# openbook_schematic.net
KiCad netlist of a schematic drawn in EAGLE
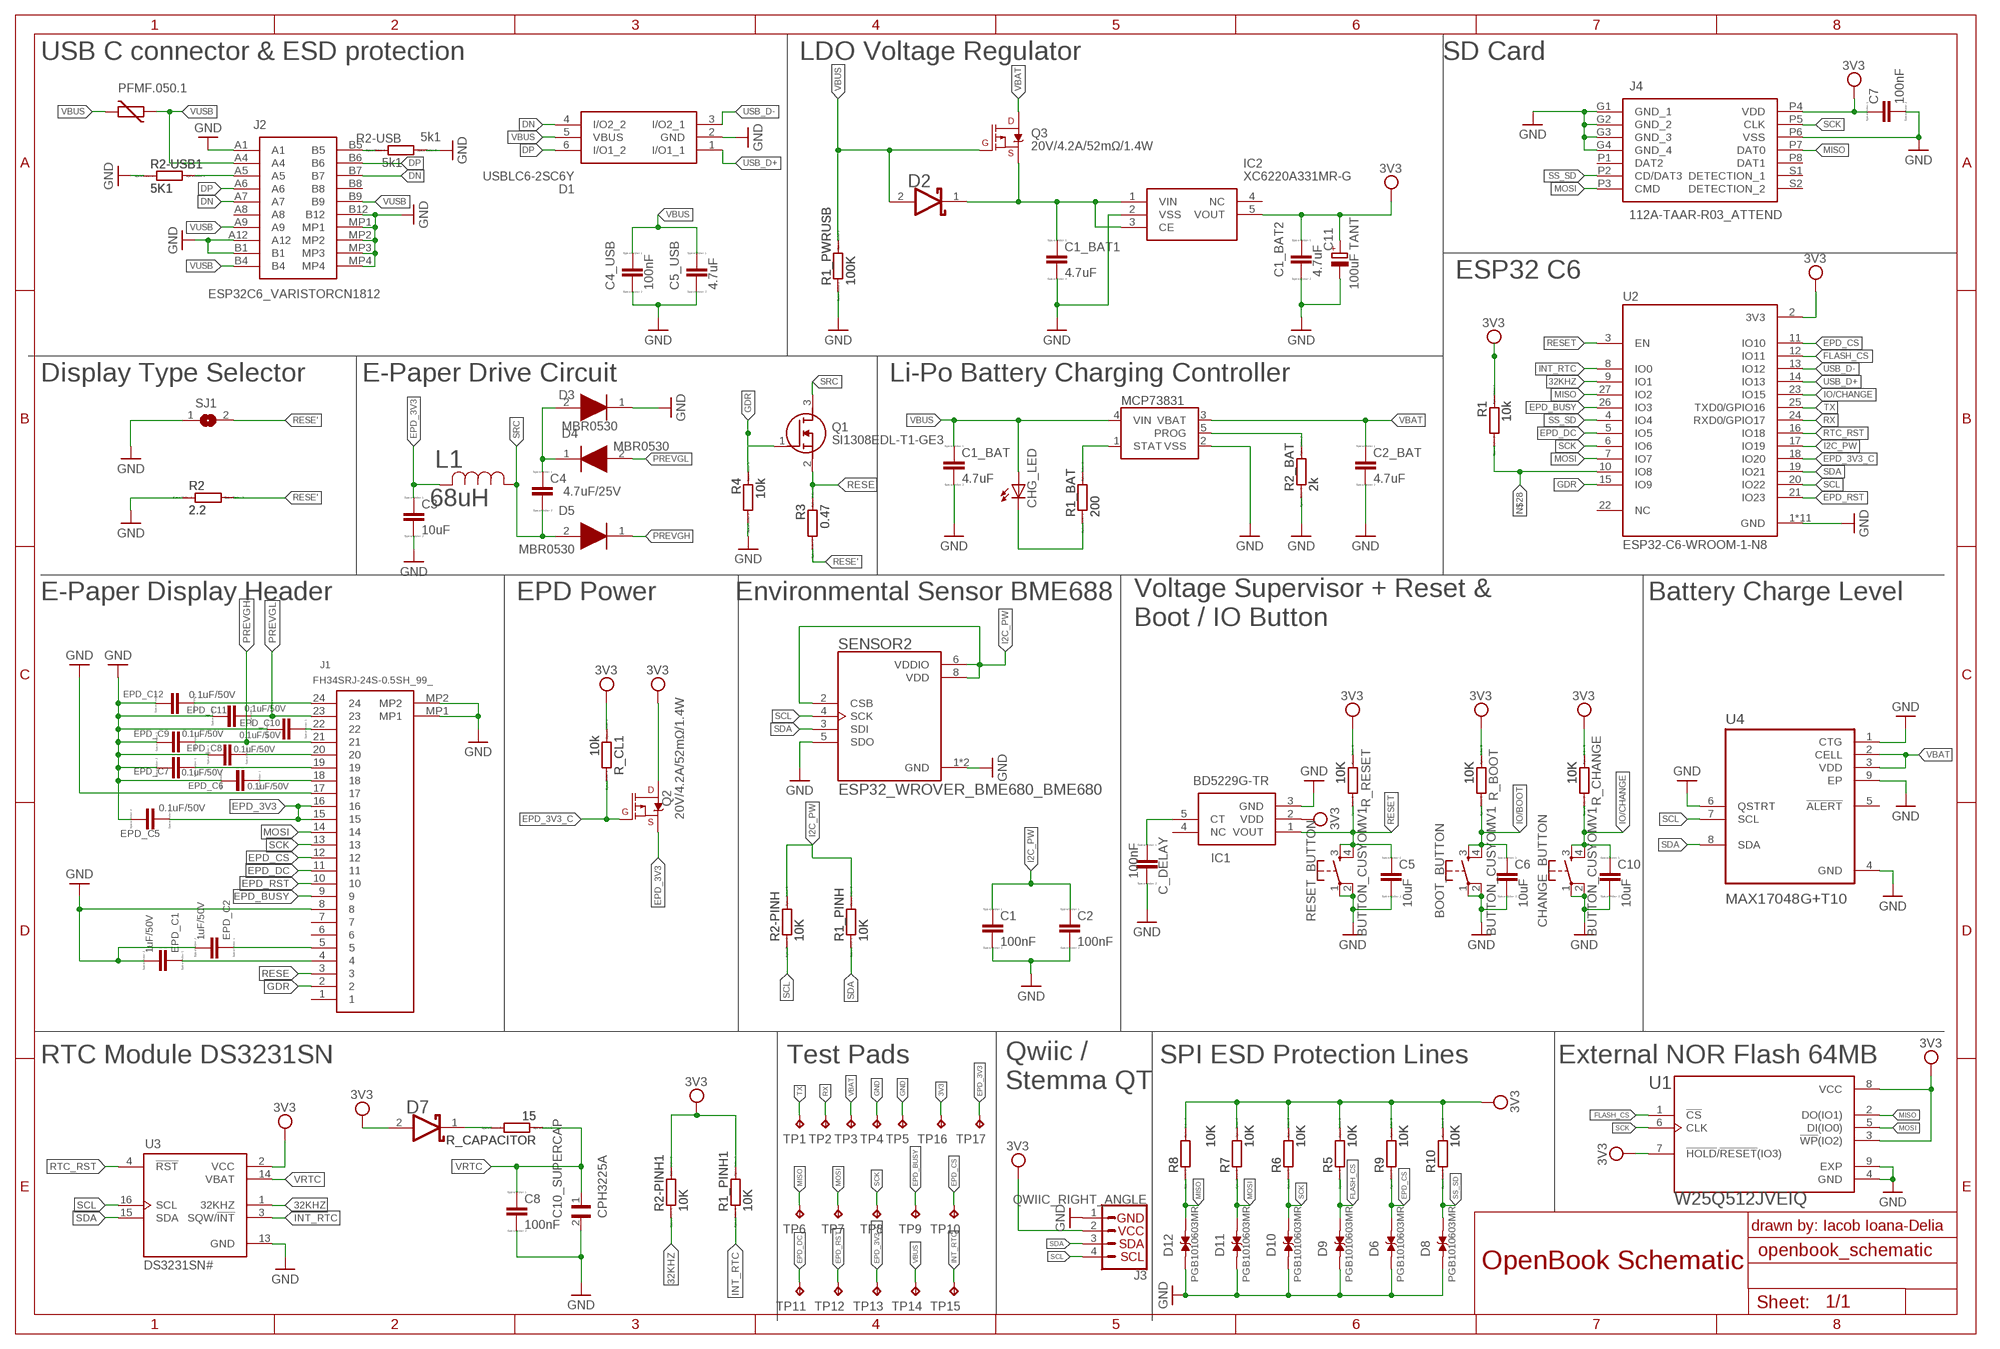
[diagram p0: schematic, sheet 1]

(export (version "E")
  (design (tool "Eeschema 10.0.6"))
  (components
    (comp (ref "BOOT_BUTTON")
      (value "BUTTON_CUSYOMV1")
      (footprint "eagle-import:MYBUTTON")
      (libsource (lib "eagle-import") (part "BUTTON_CUSYOMV1"))
    )
    (comp (ref "C1")
      (value "100nF")
      (footprint "eagle-import:ESP32_WROVER_EAGLE-LTSPICE_C0402")
      (libsource (lib "eagle-import") (part "ESP32_WROVER_EAGLE-LTSPICE_CC0402"))
    )
    (comp (ref "C1_BAT")
      (value "4.7uF")
      (footprint "eagle-import:ESP32_WROVER_EAGLE-LTSPICE_C0402")
      (libsource (lib "eagle-import") (part "ESP32_WROVER_EAGLE-LTSPICE_CC0402"))
    )
    (comp (ref "C1_BAT1")
      (value "4.7uF")
      (footprint "eagle-import:ESP32_WROVER_EAGLE-LTSPICE_C0402")
      (libsource (lib "eagle-import") (part "ESP32_WROVER_EAGLE-LTSPICE_CC0402"))
    )
    (comp (ref "C1_BAT2")
      (value "4.7uF")
      (footprint "eagle-import:ESP32_WROVER_EAGLE-LTSPICE_C0402")
      (libsource (lib "eagle-import") (part "ESP32_WROVER_EAGLE-LTSPICE_CC0402"))
    )
    (comp (ref "C2")
      (value "100nF")
      (footprint "eagle-import:ESP32_WROVER_EAGLE-LTSPICE_C0402")
      (libsource (lib "eagle-import") (part "ESP32_WROVER_EAGLE-LTSPICE_CC0402"))
    )
    (comp (ref "C2_BAT")
      (value "4.7uF")
      (footprint "eagle-import:ESP32_WROVER_EAGLE-LTSPICE_C0402")
      (libsource (lib "eagle-import") (part "ESP32_WROVER_EAGLE-LTSPICE_CC0402"))
    )
    (comp (ref "C3")
      (value "10uF")
      (footprint "eagle-import:ESP32_WROVER_EAGLE-LTSPICE_C0402")
      (libsource (lib "eagle-import") (part "ESP32_WROVER_EAGLE-LTSPICE_CC0402"))
    )
    (comp (ref "C4")
      (value "4.7uF/25V")
      (footprint "eagle-import:ESP32_WROVER_EAGLE-LTSPICE_C0402")
      (libsource (lib "eagle-import") (part "DeskAssistant_v19_v1_vf.EQLOxIDGRNyRrnCg3211Tg_ESP32_WROVER_EAGLE-LTSPICE_CC0402"))
    )
    (comp (ref "C4_USB")
      (value "100nF")
      (footprint "eagle-import:ESP32_WROVER_EAGLE-LTSPICE_C0402")
      (libsource (lib "eagle-import") (part "ESP32_WROVER_EAGLE-LTSPICE_CC0402"))
    )
    (comp (ref "C5")
      (value "10uF")
      (footprint "eagle-import:ESP32_WROVER_EAGLE-LTSPICE_C0402")
      (libsource (lib "eagle-import") (part "ESP32_WROVER_EAGLE-LTSPICE_CC0402"))
    )
    (comp (ref "C5_USB")
      (value "4.7uF")
      (footprint "eagle-import:ESP32_WROVER_EAGLE-LTSPICE_C0402")
      (libsource (lib "eagle-import") (part "ESP32_WROVER_EAGLE-LTSPICE_CC0402"))
    )
    (comp (ref "C6")
      (value "10uF")
      (footprint "eagle-import:ESP32_WROVER_EAGLE-LTSPICE_C0402")
      (libsource (lib "eagle-import") (part "ESP32_WROVER_EAGLE-LTSPICE_CC0402"))
    )
    (comp (ref "C7")
      (value "100nF")
      (footprint "eagle-import:ESP32_WROVER_EAGLE-LTSPICE_C0402")
      (libsource (lib "eagle-import") (part "ESP32_WROVER_EAGLE-LTSPICE_CC0402"))
    )
    (comp (ref "C8")
      (value "100nF")
      (footprint "eagle-import:ESP32_WROVER_EAGLE-LTSPICE_C0402")
      (libsource (lib "eagle-import") (part "ESP32_WROVER_EAGLE-LTSPICE_CC0402"))
    )
    (comp (ref "C10")
      (value "10uF")
      (footprint "eagle-import:ESP32_WROVER_EAGLE-LTSPICE_C0402")
      (libsource (lib "eagle-import") (part "ESP32_WROVER_EAGLE-LTSPICE_CC0402"))
    )
    (comp (ref "C10_SUPERCAP")
      (value "CPH3225A")
      (footprint "eagle-import:CAPCP3225X100N")
      (fields (field (name "MF") "Seiko Instruments"))
      (libsource (lib "eagle-import") (part "CPH3225A"))
    )
    (comp (ref "C11")
      (value "100uF TANT")
      (footprint "eagle-import:RCL_CT3528")
      (libsource (lib "eagle-import") (part "RCL_CPOL-EUCT3528"))
    )
    (comp (ref "CHANGE_BUTTON")
      (value "BUTTON_CUSYOMV1")
      (footprint "eagle-import:MYBUTTON")
      (libsource (lib "eagle-import") (part "BUTTON_CUSYOMV1"))
    )
    (comp (ref "CHG_LED")
      (value "ADAFRUIT_LEDCHIP-LED0603")
      (footprint "eagle-import:ADAFRUIT_CHIP-LED0603")
      (libsource (lib "eagle-import") (part "ADAFRUIT_LEDCHIP-LED0603"))
    )
    (comp (ref "C_DELAY")
      (value "100nF")
      (footprint "eagle-import:ESP32_WROVER_EAGLE-LTSPICE_C0402")
      (libsource (lib "eagle-import") (part "ESP32_WROVER_EAGLE-LTSPICE_CC0402"))
    )
    (comp (ref "D1")
      (value "USBLC6-2SC6Y")
      (footprint "eagle-import:SOT95P280X145-6N")
      (fields (field (name "MF") "STMicroelectronics"))
      (libsource (lib "eagle-import") (part "USBLC6-2SC6Y"))
    )
    (comp (ref "D2")
      (value "ESP32_WROVER_AVX---SD0805S020S1R0_AVX_SD0805S020S1R0_0_0AVX_SD0805S020S1R0_0_0")
      (footprint "eagle-import:ESP32_WROVER_AVX---SD0805S020S1R0_AVX_SD0805S020S1R0_0")
      (fields
        (field (name "DIGIKEY_PART_NUMBER") "478-7800-1-ND")
        (field (name "MF") "AVX")
        (field (name "MOUSER_PART_NUMBER") "581-SD0805S020S1R0")
      )
      (libsource (lib "eagle-import") (part "ESP32_WROVER_AVX---SD0805S020S1R0_AVX_SD0805S020S1R0_0_0AVX_SD0805S020S1R0_0_0"))
    )
    (comp (ref "D3")
      (value "MBR0530")
      (footprint "eagle-import:SOD3716X135N")
      (fields (field (name "MF") "ON Semiconductor"))
      (libsource (lib "eagle-import") (part "MBR0530"))
    )
    (comp (ref "D4")
      (value "MBR0530")
      (footprint "eagle-import:SOD3716X135N")
      (fields (field (name "MF") "ON Semiconductor"))
      (libsource (lib "eagle-import") (part "MBR0530"))
    )
    (comp (ref "D5")
      (value "MBR0530")
      (footprint "eagle-import:SOD3716X135N")
      (fields (field (name "MF") "ON Semiconductor"))
      (libsource (lib "eagle-import") (part "MBR0530"))
    )
    (comp (ref "D6")
      (value "PGB1010603MR")
      (footprint "eagle-import:DIOC1608X36N")
      (fields (field (name "MF") "Littelfuse Inc."))
      (libsource (lib "eagle-import") (part "PGB1010603MR"))
    )
    (comp (ref "D7")
      (value "ESP32_WROVER_AVX---SD0805S020S1R0_AVX_SD0805S020S1R0_0_0AVX_SD0805S020S1R0_0_0")
      (footprint "eagle-import:ESP32_WROVER_AVX---SD0805S020S1R0_AVX_SD0805S020S1R0_0")
      (fields
        (field (name "DIGIKEY_PART_NUMBER") "478-7800-1-ND")
        (field (name "MF") "AVX")
        (field (name "MOUSER_PART_NUMBER") "581-SD0805S020S1R0")
      )
      (libsource (lib "eagle-import") (part "ESP32_WROVER_AVX---SD0805S020S1R0_AVX_SD0805S020S1R0_0_0AVX_SD0805S020S1R0_0_0"))
    )
    (comp (ref "D8")
      (value "PGB1010603MR")
      (footprint "eagle-import:DIOC1608X36N")
      (fields (field (name "MF") "Littelfuse Inc."))
      (libsource (lib "eagle-import") (part "PGB1010603MR"))
    )
    (comp (ref "D9")
      (value "PGB1010603MR")
      (footprint "eagle-import:DIOC1608X36N")
      (fields (field (name "MF") "Littelfuse Inc."))
      (libsource (lib "eagle-import") (part "PGB1010603MR"))
    )
    (comp (ref "D10")
      (value "PGB1010603MR")
      (footprint "eagle-import:DIOC1608X36N")
      (fields (field (name "MF") "Littelfuse Inc."))
      (libsource (lib "eagle-import") (part "PGB1010603MR"))
    )
    (comp (ref "D11")
      (value "PGB1010603MR")
      (footprint "eagle-import:DIOC1608X36N")
      (fields (field (name "MF") "Littelfuse Inc."))
      (libsource (lib "eagle-import") (part "PGB1010603MR"))
    )
    (comp (ref "D12")
      (value "PGB1010603MR")
      (footprint "eagle-import:DIOC1608X36N")
      (fields (field (name "MF") "Littelfuse Inc."))
      (libsource (lib "eagle-import") (part "PGB1010603MR"))
    )
    (comp (ref "EPD_C1")
      (value "1uF/50V")
      (footprint "eagle-import:ESP32_WROVER_EAGLE-LTSPICE_C0402")
      (libsource (lib "eagle-import") (part "ESP32_WROVER_EAGLE-LTSPICE_CC0402"))
    )
    (comp (ref "EPD_C2")
      (value "1uF/50V")
      (footprint "eagle-import:ESP32_WROVER_EAGLE-LTSPICE_C0402")
      (libsource (lib "eagle-import") (part "ESP32_WROVER_EAGLE-LTSPICE_CC0402"))
    )
    (comp (ref "EPD_C5")
      (value "0.1uF/50V")
      (footprint "eagle-import:ESP32_WROVER_EAGLE-LTSPICE_C0402")
      (libsource (lib "eagle-import") (part "ESP32_WROVER_EAGLE-LTSPICE_CC0402"))
    )
    (comp (ref "EPD_C6")
      (value "0.1uF/50V")
      (footprint "eagle-import:ESP32_WROVER_EAGLE-LTSPICE_C0402")
      (libsource (lib "eagle-import") (part "ESP32_WROVER_EAGLE-LTSPICE_CC0402"))
    )
    (comp (ref "EPD_C7")
      (value "0.1uF/50V")
      (footprint "eagle-import:ESP32_WROVER_EAGLE-LTSPICE_C0402")
      (libsource (lib "eagle-import") (part "ESP32_WROVER_EAGLE-LTSPICE_CC0402"))
    )
    (comp (ref "EPD_C8")
      (value "0.1uF/50V")
      (footprint "eagle-import:ESP32_WROVER_EAGLE-LTSPICE_C0402")
      (libsource (lib "eagle-import") (part "ESP32_WROVER_EAGLE-LTSPICE_CC0402"))
    )
    (comp (ref "EPD_C9")
      (value "0.1uF/50V")
      (footprint "eagle-import:ESP32_WROVER_EAGLE-LTSPICE_C0402")
      (libsource (lib "eagle-import") (part "ESP32_WROVER_EAGLE-LTSPICE_CC0402"))
    )
    (comp (ref "EPD_C10")
      (value "0.1uF/50V")
      (footprint "eagle-import:ESP32_WROVER_EAGLE-LTSPICE_C0402")
      (libsource (lib "eagle-import") (part "ESP32_WROVER_EAGLE-LTSPICE_CC0402"))
    )
    (comp (ref "EPD_C11")
      (value "0.1uF/50V")
      (footprint "eagle-import:ESP32_WROVER_EAGLE-LTSPICE_C0402")
      (libsource (lib "eagle-import") (part "ESP32_WROVER_EAGLE-LTSPICE_CC0402"))
    )
    (comp (ref "EPD_C12")
      (value "0.1uF/50V")
      (footprint "eagle-import:ESP32_WROVER_EAGLE-LTSPICE_C0402")
      (libsource (lib "eagle-import") (part "ESP32_WROVER_EAGLE-LTSPICE_CC0402"))
    )
    (comp (ref "IC1")
      (value "BD5229G-TR")
      (footprint "eagle-import:SOT95P280X125-5N")
      (fields (field (name "MOUSER_PART_NUMBER") "755-BD5229G-TR"))
      (libsource (lib "eagle-import") (part "BD5229G-TR"))
    )
    (comp (ref "IC2")
      (value "XC6220A331MR-G")
      (footprint "eagle-import:SOT95P280X120-5N")
      (fields (field (name "MOUSER_PART_NUMBER") "865-XC6220A331MR-G"))
      (libsource (lib "eagle-import") (part "XC6220A331MR-G"))
    )
    (comp (ref "J1")
      (value "FH34SRJ-24S-0.5SH_99_")
      (footprint "eagle-import:FH34SRJ24S05SH99")
      (fields
        (field (name "MANUFACTURER_PART_NUMBER") "FH34SRJ-24S-0.5SH(99)")
        (field (name "MOUSER_PART_NUMBER") "798-FH34SRJ24S05SH99")
      )
      (libsource (lib "eagle-import") (part "FH34SRJ-24S-0.5SH_99_"))
    )
    (comp (ref "J2")
      (value "SAMACSYS_PARTS_USB4110-GF-A")
      (footprint "eagle-import:SAMACSYS_PARTS_USB4110GFA")
      (fields
        (field (name "MANUFACTURER_PART_NUMBER") "USB4110-GF-A")
        (field (name "MOUSER_PART_NUMBER") "640-USB4110-GF-A")
      )
      (libsource (lib "eagle-import") (part "SAMACSYS_PARTS_USB4110-GF-A"))
    )
    (comp (ref "J3")
      (value "QWIIC_RIGHT_ANGLE")
      (footprint "eagle-import:JST04_1MM_RA")
      (libsource (lib "eagle-import") (part "QWIIC_CONNECTORJS-1MM"))
    )
    (comp (ref "J4")
      (value "112A-TAAR-R03_ATTEND")
      (footprint "eagle-import:112ATAARR03ATTEND")
      (fields (field (name "MANUFACTURER_PART_NUMBER") "112A-TAAR-R03 ATTEND"))
      (libsource (lib "eagle-import") (part "112A-TAAR-R03_ATTEND"))
    )
    (comp (ref "L1")
      (value "68uH")
      (footprint "eagle-import:IND_4828-WE-TPC_WRE")
      (fields
        (field (name "MANUFACTURER_PART_NUMBER") "744043680")
        (field (name "COPYRIGHT") "Copyright (C) 2024 Ultra Librarian. All rights reserved.")
      )
      (libsource (lib "eagle-import") (part "744043680IND_4828-WE-TPC_WRE"))
    )
    (comp (ref "MCP73831")
      (value "ESP32_WROVER_SPARKFUN-IC-POWER_MCP73831")
      (footprint "eagle-import:ESP32_WROVER_SPARKFUN-IC-POWER_SOT23-5")
      (libsource (lib "eagle-import") (part "ESP32_WROVER_SPARKFUN-IC-POWER_MCP73831"))
    )
    (comp (ref "PFMF.050.1")
      (value "ESP32C6_VARISTORCN1812")
      (footprint "eagle-import:ESP32C6_VARISTOR_CT_CN1812")
      (libsource (lib "eagle-import") (part "ESP32C6_VARISTORCN1812"))
    )
    (comp (ref "Q1")
      (value "SI1308EDL-T1-GE3")
      (footprint "eagle-import:SOT65P210X110-3N")
      (fields (field (name "MF") "Vishay Siliconix"))
      (libsource (lib "eagle-import") (part "SI1308EDL-T1-GE3"))
    )
    (comp (ref "Q2")
      (value "20V/4.2A/52mΩ/1.4W")
      (footprint "eagle-import:ESP32_WROVER_SPARKFUN-DISCRETESEMI_SOT23-3")
      (libsource (lib "eagle-import") (part "ESP32_WROVER_SPARKFUN-DISCRETESEMI_MOSFET_PCH-DMG2305UX-7"))
    )
    (comp (ref "Q3")
      (value "20V/4.2A/52mΩ/1.4W")
      (footprint "eagle-import:ESP32_WROVER_SPARKFUN-DISCRETESEMI_SOT23-3")
      (libsource (lib "eagle-import") (part "ESP32_WROVER_SPARKFUN-DISCRETESEMI_MOSFET_PCH-DMG2305UX-7"))
    )
    (comp (ref "R1")
      (value "10k")
      (footprint "eagle-import:ESP32_WROVER_EAGLE-LTSPICE_R0402")
      (libsource (lib "eagle-import") (part "DeskAssistant_v19_v1_vf.EQLOxIDGRNyRrnCg3211Tg_ESP32_WROVER_EAGLE-LTSPICE_RR0402"))
    )
    (comp (ref "R1_BAT")
      (value "200")
      (footprint "eagle-import:ESP32_WROVER_EAGLE-LTSPICE_R0402")
      (libsource (lib "eagle-import") (part "DeskAssistant_v19_v1_vf.EQLOxIDGRNyRrnCg3211Tg_ESP32_WROVER_EAGLE-LTSPICE_RR0402"))
    )
    (comp (ref "R1_PINH")
      (value "10K")
      (footprint "eagle-import:ESP32_WROVER_EAGLE-LTSPICE_R0402")
      (libsource (lib "eagle-import") (part "DeskAssistant_v19_v1_vf.EQLOxIDGRNyRrnCg3211Tg_ESP32_WROVER_EAGLE-LTSPICE_RR0402"))
    )
    (comp (ref "R1_PINH1")
      (value "10K")
      (footprint "eagle-import:ESP32_WROVER_EAGLE-LTSPICE_R0402")
      (libsource (lib "eagle-import") (part "DeskAssistant_v19_v1_vf.EQLOxIDGRNyRrnCg3211Tg_ESP32_WROVER_EAGLE-LTSPICE_RR0402"))
    )
    (comp (ref "R1_PWRUSB")
      (value "100K")
      (footprint "eagle-import:ESP32_WROVER_EAGLE-LTSPICE_R0402")
      (libsource (lib "eagle-import") (part "DeskAssistant_v19_v1_vf.EQLOxIDGRNyRrnCg3211Tg_ESP32_WROVER_EAGLE-LTSPICE_RR0402"))
    )
    (comp (ref "R2")
      (value "2.2")
      (footprint "eagle-import:ESP32_WROVER_EAGLE-LTSPICE_R0402")
      (libsource (lib "eagle-import") (part "DeskAssistant_v19_v1_vf.EQLOxIDGRNyRrnCg3211Tg_ESP32_WROVER_EAGLE-LTSPICE_RR0402"))
    )
    (comp (ref "R2-PINH")
      (value "10K")
      (footprint "eagle-import:ESP32_WROVER_EAGLE-LTSPICE_R0402")
      (libsource (lib "eagle-import") (part "DeskAssistant_v19_v1_vf.EQLOxIDGRNyRrnCg3211Tg_ESP32_WROVER_EAGLE-LTSPICE_RR0402"))
    )
    (comp (ref "R2-PINH1")
      (value "10K")
      (footprint "eagle-import:ESP32_WROVER_EAGLE-LTSPICE_R0402")
      (libsource (lib "eagle-import") (part "DeskAssistant_v19_v1_vf.EQLOxIDGRNyRrnCg3211Tg_ESP32_WROVER_EAGLE-LTSPICE_RR0402"))
    )
    (comp (ref "R2-USB")
      (value "5k1")
      (footprint "eagle-import:ESP32_WROVER_EAGLE-LTSPICE_R0402")
      (libsource (lib "eagle-import") (part "DeskAssistant_v19_v1_vf.EQLOxIDGRNyRrnCg3211Tg_ESP32_WROVER_EAGLE-LTSPICE_RR0402"))
    )
    (comp (ref "R2-USB1")
      (value "5K1")
      (footprint "eagle-import:ESP32_WROVER_EAGLE-LTSPICE_R0402")
      (libsource (lib "eagle-import") (part "DeskAssistant_v19_v1_vf.EQLOxIDGRNyRrnCg3211Tg_ESP32_WROVER_EAGLE-LTSPICE_RR0402"))
    )
    (comp (ref "R2_BAT")
      (value "2k")
      (footprint "eagle-import:ESP32_WROVER_EAGLE-LTSPICE_R0402")
      (libsource (lib "eagle-import") (part "DeskAssistant_v19_v1_vf.EQLOxIDGRNyRrnCg3211Tg_ESP32_WROVER_EAGLE-LTSPICE_RR0402"))
    )
    (comp (ref "R3")
      (value "0.47")
      (footprint "eagle-import:ESP32_WROVER_EAGLE-LTSPICE_R0402")
      (libsource (lib "eagle-import") (part "ESP32_WROVER_EAGLE-LTSPICE_RR0402"))
    )
    (comp (ref "R4")
      (value "10k")
      (footprint "eagle-import:ESP32_WROVER_EAGLE-LTSPICE_R0402")
      (libsource (lib "eagle-import") (part "ESP32_WROVER_EAGLE-LTSPICE_RR0402"))
    )
    (comp (ref "R5")
      (value "10K")
      (footprint "eagle-import:ESP32_WROVER_EAGLE-LTSPICE_R0402")
      (libsource (lib "eagle-import") (part "DeskAssistant_v19_v1_vf.EQLOxIDGRNyRrnCg3211Tg_ESP32_WROVER_EAGLE-LTSPICE_RR0402"))
    )
    (comp (ref "R6")
      (value "10K")
      (footprint "eagle-import:ESP32_WROVER_EAGLE-LTSPICE_R0402")
      (libsource (lib "eagle-import") (part "DeskAssistant_v19_v1_vf.EQLOxIDGRNyRrnCg3211Tg_ESP32_WROVER_EAGLE-LTSPICE_RR0402"))
    )
    (comp (ref "R7")
      (value "10K")
      (footprint "eagle-import:ESP32_WROVER_EAGLE-LTSPICE_R0402")
      (libsource (lib "eagle-import") (part "DeskAssistant_v19_v1_vf.EQLOxIDGRNyRrnCg3211Tg_ESP32_WROVER_EAGLE-LTSPICE_RR0402"))
    )
    (comp (ref "R8")
      (value "10K")
      (footprint "eagle-import:ESP32_WROVER_EAGLE-LTSPICE_R0402")
      (libsource (lib "eagle-import") (part "DeskAssistant_v19_v1_vf.EQLOxIDGRNyRrnCg3211Tg_ESP32_WROVER_EAGLE-LTSPICE_RR0402"))
    )
    (comp (ref "R9")
      (value "10K")
      (footprint "eagle-import:ESP32_WROVER_EAGLE-LTSPICE_R0402")
      (libsource (lib "eagle-import") (part "DeskAssistant_v19_v1_vf.EQLOxIDGRNyRrnCg3211Tg_ESP32_WROVER_EAGLE-LTSPICE_RR0402"))
    )
    (comp (ref "R10")
      (value "10K")
      (footprint "eagle-import:ESP32_WROVER_EAGLE-LTSPICE_R0402")
      (libsource (lib "eagle-import") (part "DeskAssistant_v19_v1_vf.EQLOxIDGRNyRrnCg3211Tg_ESP32_WROVER_EAGLE-LTSPICE_RR0402"))
    )
    (comp (ref "RESET_BUTTON")
      (value "BUTTON_CUSYOMV1")
      (footprint "eagle-import:MYBUTTON")
      (libsource (lib "eagle-import") (part "BUTTON_CUSYOMV1"))
    )
    (comp (ref "R_BOOT")
      (value "10K")
      (footprint "eagle-import:ESP32_WROVER_EAGLE-LTSPICE_R0402")
      (libsource (lib "eagle-import") (part "DeskAssistant_v19_v1_vf.EQLOxIDGRNyRrnCg3211Tg_ESP32_WROVER_EAGLE-LTSPICE_RR0402"))
    )
    (comp (ref "R_CAPACITOR")
      (value "15")
      (footprint "eagle-import:ESP32_WROVER_EAGLE-LTSPICE_R0402")
      (libsource (lib "eagle-import") (part "DeskAssistant_v19_v1_vf.EQLOxIDGRNyRrnCg3211Tg_ESP32_WROVER_EAGLE-LTSPICE_RR0402"))
    )
    (comp (ref "R_CHANGE")
      (value "10K")
      (footprint "eagle-import:ESP32_WROVER_EAGLE-LTSPICE_R0402")
      (libsource (lib "eagle-import") (part "DeskAssistant_v19_v1_vf.EQLOxIDGRNyRrnCg3211Tg_ESP32_WROVER_EAGLE-LTSPICE_RR0402"))
    )
    (comp (ref "R_CL1")
      (value "10k")
      (footprint "eagle-import:ESP32_WROVER_EAGLE-LTSPICE_R0402")
      (libsource (lib "eagle-import") (part "DeskAssistant_v19_v1_vf.EQLOxIDGRNyRrnCg3211Tg_ESP32_WROVER_EAGLE-LTSPICE_RR0402"))
    )
    (comp (ref "R_RESET")
      (value "10K")
      (footprint "eagle-import:ESP32_WROVER_EAGLE-LTSPICE_R0402")
      (libsource (lib "eagle-import") (part "DeskAssistant_v19_v1_vf.EQLOxIDGRNyRrnCg3211Tg_ESP32_WROVER_EAGLE-LTSPICE_RR0402"))
    )
    (comp (ref "SENSOR2")
      (value "ESP32_WROVER_BME680_BME680")
      (footprint "eagle-import:ESP32_WROVER_BME680_PSON80P300X300X100-8N")
      (fields (field (name "MF") "Bosch Sensortec") (field (name "MP") "BME680"))
      (libsource (lib "eagle-import") (part "ESP32_WROVER_BME680_BME680"))
    )
    (comp (ref "SJ1") (value "SJ") (footprint "eagle-import:SJ") (libsource (lib "eagle-import") (part "SJ")))
    (comp (ref "TP1")
      (value "TPTP20R")
      (footprint "eagle-import:TP20R")
      (libsource (lib "eagle-import") (part "TPTP20R"))
    )
    (comp (ref "TP2")
      (value "TPTP20R")
      (footprint "eagle-import:TP20R")
      (libsource (lib "eagle-import") (part "TPTP20R"))
    )
    (comp (ref "TP3")
      (value "TPTP20R")
      (footprint "eagle-import:TP20R")
      (libsource (lib "eagle-import") (part "TPTP20R"))
    )
    (comp (ref "TP4")
      (value "TPTP20R")
      (footprint "eagle-import:TP20R")
      (libsource (lib "eagle-import") (part "TPTP20R"))
    )
    (comp (ref "TP5")
      (value "TPTP20R")
      (footprint "eagle-import:TP20R")
      (libsource (lib "eagle-import") (part "TPTP20R"))
    )
    (comp (ref "TP6")
      (value "TPTP20R")
      (footprint "eagle-import:TP20R")
      (libsource (lib "eagle-import") (part "TPTP20R"))
    )
    (comp (ref "TP7")
      (value "TPTP20R")
      (footprint "eagle-import:TP20R")
      (libsource (lib "eagle-import") (part "TPTP20R"))
    )
    (comp (ref "TP8")
      (value "TPTP20R")
      (footprint "eagle-import:TP20R")
      (libsource (lib "eagle-import") (part "TPTP20R"))
    )
    (comp (ref "TP9")
      (value "TPTP20R")
      (footprint "eagle-import:TP20R")
      (libsource (lib "eagle-import") (part "TPTP20R"))
    )
    (comp (ref "TP10")
      (value "TPTP20R")
      (footprint "eagle-import:TP20R")
      (libsource (lib "eagle-import") (part "TPTP20R"))
    )
    (comp (ref "TP11")
      (value "TPTP20R")
      (footprint "eagle-import:TP20R")
      (libsource (lib "eagle-import") (part "TPTP20R"))
    )
    (comp (ref "TP12")
      (value "TPTP20R")
      (footprint "eagle-import:TP20R")
      (libsource (lib "eagle-import") (part "TPTP20R"))
    )
    (comp (ref "TP13")
      (value "TPTP20R")
      (footprint "eagle-import:TP20R")
      (libsource (lib "eagle-import") (part "TPTP20R"))
    )
    (comp (ref "TP14")
      (value "TPTP20R")
      (footprint "eagle-import:TP20R")
      (libsource (lib "eagle-import") (part "TPTP20R"))
    )
    (comp (ref "TP15")
      (value "TPTP20R")
      (footprint "eagle-import:TP20R")
      (libsource (lib "eagle-import") (part "TPTP20R"))
    )
    (comp (ref "TP16")
      (value "TPTP20R")
      (footprint "eagle-import:TP20R")
      (libsource (lib "eagle-import") (part "TPTP20R"))
    )
    (comp (ref "TP17")
      (value "TPTP20R")
      (footprint "eagle-import:TP20R")
      (libsource (lib "eagle-import") (part "TPTP20R"))
    )
    (comp (ref "U1")
      (value "W25Q512JVEIQ")
      (footprint "eagle-import:SON127P600X800X80-9N")
      (fields (field (name "MF") "Winbond Electronics"))
      (libsource (lib "eagle-import") (part "W25Q512JVEIQ"))
    )
    (comp (ref "U2")
      (value "ESP32-C6-WROOM-1-N8")
      (footprint "eagle-import:XCVR_ESP32-C6-WROOM-1-N8")
      (fields (field (name "MF") "Espressif Systems"))
      (libsource (lib "eagle-import") (part "ESP32-C6-WROOM-1-N8"))
    )
    (comp (ref "U3")
      (value "DS3231SN#")
      (footprint "eagle-import:SOIC127P1032X265-16N")
      (fields (field (name "MF") "Analog Devices"))
      (libsource (lib "eagle-import") (part "DS3231SN#"))
    )
    (comp (ref "U4")
      (value "MAX17048G+T10")
      (footprint "eagle-import:SON50P200X200X80-9N")
      (fields (field (name "MF") "Analog Devices"))
      (libsource (lib "eagle-import") (part "MAX17048G+T10"))
    )
  )
  (nets
    (net (code "1") (name "3V3") (class "Default")
      (node (ref "C11") (pin "+") (pinfunction "+_+") (pintype "passive"))
      (node (ref "C1_BAT2") (pin "1") (pinfunction "1_1") (pintype "passive"))
      (node (ref "C7") (pin "1") (pinfunction "1_1") (pintype "passive"))
      (node (ref "D7") (pin "2") (pinfunction "ANODE_2") (pintype "bidirectional"))
      (node (ref "IC1") (pin "2") (pinfunction "VDD_2") (pintype "bidirectional"))
      (node (ref "IC2") (pin "5") (pinfunction "VOUT_5") (pintype "bidirectional"))
      (node (ref "J3") (pin "2") (pinfunction "2_2") (pintype "power_in"))
      (node (ref "J4") (pin "P4") (pinfunction "VDD_P4") (pintype "bidirectional"))
      (node (ref "Q2") (pin "3") (pinfunction "D_3") (pintype "bidirectional"))
      (node (ref "R1") (pin "1") (pinfunction "1_1") (pintype "passive"))
      (node (ref "R10") (pin "2") (pinfunction "2_2") (pintype "passive"))
      (node (ref "R1_PINH1") (pin "2") (pinfunction "2_2") (pintype "passive"))
      (node (ref "R2-PINH1") (pin "2") (pinfunction "2_2") (pintype "passive"))
      (node (ref "R5") (pin "2") (pinfunction "2_2") (pintype "passive"))
      (node (ref "R6") (pin "2") (pinfunction "2_2") (pintype "passive"))
      (node (ref "R7") (pin "2") (pinfunction "2_2") (pintype "passive"))
      (node (ref "R8") (pin "2") (pinfunction "2_2") (pintype "passive"))
      (node (ref "R9") (pin "2") (pinfunction "2_2") (pintype "passive"))
      (node (ref "R_BOOT") (pin "1") (pinfunction "1_1") (pintype "passive"))
      (node (ref "R_CHANGE") (pin "1") (pinfunction "1_1") (pintype "passive"))
      (node (ref "R_CL1") (pin "1") (pinfunction "1_1") (pintype "passive"))
      (node (ref "R_RESET") (pin "1") (pinfunction "1_1") (pintype "passive"))
      (node (ref "TP16") (pin "TP") (pinfunction "TP_TP") (pintype "input"))
      (node (ref "U1") (pin "3") (pinfunction "~{WP}(IO2)_3") (pintype "bidirectional"))
      (node (ref "U1") (pin "7") (pinfunction "~{HOLD}/~{RESET}(IO3)_7") (pintype "bidirectional"))
      (node (ref "U1") (pin "8") (pinfunction "VCC_8") (pintype "power_in"))
      (node (ref "U2") (pin "2") (pinfunction "3V3_2") (pintype "power_in"))
      (node (ref "U3") (pin "2") (pinfunction "VCC_2") (pintype "power_in"))
    )
    (net (code "2") (name "32KHZ") (class "Default")
      (node (ref "R2-PINH1") (pin "1") (pinfunction "1_1") (pintype "passive"))
      (node (ref "U2") (pin "9") (pinfunction "IO1_9") (pintype "bidirectional"))
      (node (ref "U3") (pin "1") (pinfunction "32KHZ_1") (pintype "output"))
    )
    (net (code "3") (name "DN") (class "Default")
      (node (ref "D1") (pin "4") (pinfunction "I/O2_2_4") (pintype "bidirectional"))
      (node (ref "J2") (pin "A7") (pinfunction "A7_A7") (pintype "bidirectional"))
      (node (ref "J2") (pin "B7") (pinfunction "B7_B7") (pintype "bidirectional"))
    )
    (net (code "4") (name "DP") (class "Default")
      (node (ref "D1") (pin "6") (pinfunction "I/O1_2_6") (pintype "bidirectional"))
      (node (ref "J2") (pin "A6") (pinfunction "A6_A6") (pintype "bidirectional"))
      (node (ref "J2") (pin "B6") (pinfunction "B6_B6") (pintype "bidirectional"))
    )
    (net (code "5") (name "EPD_3V3") (class "Default")
      (node (ref "C3") (pin "1") (pinfunction "1_1") (pintype "passive"))
      (node (ref "EPD_C5") (pin "1") (pinfunction "1_1") (pintype "passive"))
      (node (ref "J1") (pin "15") (pinfunction "15_15") (pintype "bidirectional"))
      (node (ref "J1") (pin "16") (pinfunction "16_16") (pintype "bidirectional"))
      (node (ref "L1") (pin "2") (pinfunction "2_2") (pintype "passive"))
      (node (ref "Q2") (pin "2") (pinfunction "S_2") (pintype "bidirectional"))
      (node (ref "TP17") (pin "TP") (pinfunction "TP_TP") (pintype "input"))
    )
    (net (code "6") (name "EPD_3V3_C") (class "Default")
      (node (ref "Q2") (pin "1") (pinfunction "G_1") (pintype "bidirectional"))
      (node (ref "R_CL1") (pin "2") (pinfunction "2_2") (pintype "passive"))
      (node (ref "TP13") (pin "TP") (pinfunction "TP_TP") (pintype "input"))
      (node (ref "U2") (pin "18") (pinfunction "IO20_18") (pintype "bidirectional"))
    )
    (net (code "7") (name "EPD_BUSY") (class "Default")
      (node (ref "J1") (pin "9") (pinfunction "9_9") (pintype "bidirectional"))
      (node (ref "TP9") (pin "TP") (pinfunction "TP_TP") (pintype "input"))
      (node (ref "U2") (pin "26") (pinfunction "IO3_26") (pintype "bidirectional"))
    )
    (net (code "8") (name "EPD_CS") (class "Default")
      (node (ref "D6") (pin "2") (pinfunction "2_2") (pintype "passive"))
      (node (ref "J1") (pin "12") (pinfunction "12_12") (pintype "bidirectional"))
      (node (ref "R9") (pin "1") (pinfunction "1_1") (pintype "passive"))
      (node (ref "TP10") (pin "TP") (pinfunction "TP_TP") (pintype "input"))
      (node (ref "U2") (pin "11") (pinfunction "IO10_11") (pintype "bidirectional"))
    )
    (net (code "9") (name "EPD_DC") (class "Default")
      (node (ref "J1") (pin "11") (pinfunction "11_11") (pintype "bidirectional"))
      (node (ref "TP11") (pin "TP") (pinfunction "TP_TP") (pintype "input"))
      (node (ref "U2") (pin "5") (pinfunction "IO5_5") (pintype "bidirectional"))
    )
    (net (code "10") (name "EPD_RST") (class "Default")
      (node (ref "J1") (pin "10") (pinfunction "10_10") (pintype "bidirectional"))
      (node (ref "TP12") (pin "TP") (pinfunction "TP_TP") (pintype "input"))
      (node (ref "U2") (pin "21") (pinfunction "IO23_21") (pintype "bidirectional"))
    )
    (net (code "11") (name "FLASH_CS") (class "Default")
      (node (ref "D9") (pin "2") (pinfunction "2_2") (pintype "passive"))
      (node (ref "R5") (pin "1") (pinfunction "1_1") (pintype "passive"))
      (node (ref "U1") (pin "1") (pinfunction "~{CS}_1") (pintype "input"))
      (node (ref "U2") (pin "12") (pinfunction "IO11_12") (pintype "bidirectional"))
    )
    (net (code "12") (name "GDR") (class "Default")
      (node (ref "J1") (pin "2") (pinfunction "2_2") (pintype "bidirectional"))
      (node (ref "Q1") (pin "1") (pinfunction "G_1") (pintype "bidirectional"))
      (node (ref "R4") (pin "1") (pinfunction "1_1") (pintype "passive"))
      (node (ref "U2") (pin "15") (pinfunction "IO9_15") (pintype "bidirectional"))
    )
    (net (code "13") (name "GND") (class "Default")
      (node (ref "BOOT_BUTTON") (pin "1") (pinfunction "1_1") (pintype "passive"))
      (node (ref "BOOT_BUTTON") (pin "2") (pinfunction "2_2") (pintype "passive"))
      (node (ref "C1") (pin "2") (pinfunction "2_2") (pintype "passive"))
      (node (ref "C10") (pin "2") (pinfunction "2_2") (pintype "passive"))
      (node (ref "C10_SUPERCAP") (pin "2") (pinfunction "2_2") (pintype "passive"))
      (node (ref "C11") (pin "-") (pinfunction "-_-") (pintype "passive"))
      (node (ref "C1_BAT") (pin "2") (pinfunction "2_2") (pintype "passive"))
      (node (ref "C1_BAT1") (pin "2") (pinfunction "2_2") (pintype "passive"))
      (node (ref "C1_BAT2") (pin "2") (pinfunction "2_2") (pintype "passive"))
      (node (ref "C2") (pin "2") (pinfunction "2_2") (pintype "passive"))
      (node (ref "C2_BAT") (pin "2") (pinfunction "2_2") (pintype "passive"))
      (node (ref "C3") (pin "2") (pinfunction "2_2") (pintype "passive"))
      (node (ref "C4_USB") (pin "2") (pinfunction "2_2") (pintype "passive"))
      (node (ref "C5") (pin "2") (pinfunction "2_2") (pintype "passive"))
      (node (ref "C5_USB") (pin "2") (pinfunction "2_2") (pintype "passive"))
      (node (ref "C6") (pin "2") (pinfunction "2_2") (pintype "passive"))
      (node (ref "C7") (pin "2") (pinfunction "2_2") (pintype "passive"))
      (node (ref "C8") (pin "2") (pinfunction "2_2") (pintype "passive"))
      (node (ref "CHANGE_BUTTON") (pin "1") (pinfunction "1_1") (pintype "passive"))
      (node (ref "CHANGE_BUTTON") (pin "2") (pinfunction "2_2") (pintype "passive"))
      (node (ref "C_DELAY") (pin "2") (pinfunction "2_2") (pintype "passive"))
      (node (ref "D1") (pin "2") (pinfunction "GND_2") (pintype "bidirectional"))
      (node (ref "D10") (pin "1") (pinfunction "1_1") (pintype "passive"))
      (node (ref "D11") (pin "1") (pinfunction "1_1") (pintype "passive"))
      (node (ref "D12") (pin "1") (pinfunction "1_1") (pintype "passive"))
      (node (ref "D3") (pin "1") (pinfunction "K_1") (pintype "bidirectional"))
      (node (ref "D6") (pin "1") (pinfunction "1_1") (pintype "passive"))
      (node (ref "D8") (pin "1") (pinfunction "1_1") (pintype "passive"))
      (node (ref "D9") (pin "1") (pinfunction "1_1") (pintype "passive"))
      (node (ref "EPD_C1") (pin "2") (pinfunction "2_2") (pintype "passive"))
      (node (ref "EPD_C10") (pin "2") (pinfunction "2_2") (pintype "passive"))
      (node (ref "EPD_C11") (pin "2") (pinfunction "2_2") (pintype "passive"))
      (node (ref "EPD_C12") (pin "2") (pinfunction "2_2") (pintype "passive"))
      (node (ref "EPD_C2") (pin "2") (pinfunction "2_2") (pintype "passive"))
      (node (ref "EPD_C5") (pin "2") (pinfunction "2_2") (pintype "passive"))
      (node (ref "EPD_C6") (pin "2") (pinfunction "2_2") (pintype "passive"))
      (node (ref "EPD_C7") (pin "2") (pinfunction "2_2") (pintype "passive"))
      (node (ref "EPD_C8") (pin "2") (pinfunction "2_2") (pintype "passive"))
      (node (ref "EPD_C9") (pin "2") (pinfunction "2_2") (pintype "passive"))
      (node (ref "IC1") (pin "3") (pinfunction "GND_3") (pintype "bidirectional"))
      (node (ref "IC2") (pin "2") (pinfunction "VSS_2") (pintype "bidirectional"))
      (node (ref "J1") (pin "17") (pinfunction "17_17") (pintype "bidirectional"))
      (node (ref "J1") (pin "8") (pinfunction "8_8") (pintype "bidirectional"))
      (node (ref "J1") (pin "MP1") (pinfunction "MP1_MP1") (pintype "bidirectional"))
      (node (ref "J1") (pin "MP2") (pinfunction "MP2_MP2") (pintype "bidirectional"))
      (node (ref "J2") (pin "A1") (pinfunction "A1_A1") (pintype "bidirectional"))
      (node (ref "J2") (pin "A12") (pinfunction "A12_A12") (pintype "bidirectional"))
      (node (ref "J2") (pin "B1") (pinfunction "B1_B1") (pintype "bidirectional"))
      (node (ref "J2") (pin "B12") (pinfunction "B12_B12") (pintype "bidirectional"))
      (node (ref "J2") (pin "MP1") (pinfunction "MP1_MP1") (pintype "bidirectional"))
      (node (ref "J2") (pin "MP2") (pinfunction "MP2_MP2") (pintype "bidirectional"))
      (node (ref "J2") (pin "MP3") (pinfunction "MP3_MP3") (pintype "bidirectional"))
      (node (ref "J2") (pin "MP4") (pinfunction "MP4_MP4") (pintype "bidirectional"))
      (node (ref "J3") (pin "1") (pinfunction "1_1") (pintype "power_in"))
      (node (ref "J4") (pin "G1") (pinfunction "GND_1_G1") (pintype "bidirectional"))
      (node (ref "J4") (pin "G2") (pinfunction "GND_2_G2") (pintype "bidirectional"))
      (node (ref "J4") (pin "G3") (pinfunction "GND_3_G3") (pintype "bidirectional"))
      (node (ref "J4") (pin "G4") (pinfunction "GND_4_G4") (pintype "bidirectional"))
      (node (ref "J4") (pin "P6") (pinfunction "VSS_P6") (pintype "bidirectional"))
      (node (ref "MCP73831") (pin "2") (pinfunction "VSS_2") (pintype "power_in"))
      (node (ref "R1_PWRUSB") (pin "1") (pinfunction "1_1") (pintype "passive"))
      (node (ref "R2") (pin "1") (pinfunction "1_1") (pintype "passive"))
      (node (ref "R2-USB") (pin "2") (pinfunction "2_2") (pintype "passive"))
      (node (ref "R2-USB1") (pin "1") (pinfunction "1_1") (pintype "passive"))
      (node (ref "R2_BAT") (pin "1") (pinfunction "1_1") (pintype "passive"))
      (node (ref "R4") (pin "2") (pinfunction "2_2") (pintype "passive"))
      (node (ref "RESET_BUTTON") (pin "1") (pinfunction "1_1") (pintype "passive"))
      (node (ref "RESET_BUTTON") (pin "2") (pinfunction "2_2") (pintype "passive"))
      (node (ref "SENSOR2") (pin "1") (pinfunction "GND_1") (pintype "power_in"))
      (node (ref "SENSOR2") (pin "5") (pinfunction "SDO_5") (pintype "bidirectional"))
      (node (ref "SENSOR2") (pin "7") (pinfunction "GND_7") (pintype "power_in"))
      (node (ref "SJ1") (pin "1") (pinfunction "1_1") (pintype "passive"))
      (node (ref "TP4") (pin "TP") (pinfunction "TP_TP") (pintype "input"))
      (node (ref "TP5") (pin "TP") (pinfunction "TP_TP") (pintype "input"))
      (node (ref "U1") (pin "4") (pinfunction "GND_4") (pintype "power_in"))
      (node (ref "U1") (pin "9") (pinfunction "EXP_9") (pintype "passive"))
      (node (ref "U2") (pin "1") (pinfunction "GND_1") (pintype "power_in"))
      (node (ref "U2") (pin "28") (pinfunction "GND_28") (pintype "power_in"))
      (node (ref "U2") (pin "29_1") (pinfunction "GND_29_1") (pintype "power_in"))
      (node (ref "U2") (pin "29_2") (pinfunction "GND_29_2") (pintype "power_in"))
      (node (ref "U2") (pin "29_3") (pinfunction "GND_29_3") (pintype "power_in"))
      (node (ref "U2") (pin "29_4") (pinfunction "GND_29_4") (pintype "power_in"))
      (node (ref "U2") (pin "29_5") (pinfunction "GND_29_5") (pintype "power_in"))
      (node (ref "U2") (pin "29_6") (pinfunction "GND_29_6") (pintype "power_in"))
      (node (ref "U2") (pin "29_7") (pinfunction "GND_29_7") (pintype "power_in"))
      (node (ref "U2") (pin "29_8") (pinfunction "GND_29_8") (pintype "power_in"))
      (node (ref "U2") (pin "29_9") (pinfunction "GND_29_9") (pintype "power_in"))
      (node (ref "U3") (pin "13") (pinfunction "GND_13") (pintype "power_in"))
      (node (ref "U4") (pin "1") (pinfunction "CTG_1") (pintype "power_in"))
      (node (ref "U4") (pin "4") (pinfunction "GND_4") (pintype "power_in"))
      (node (ref "U4") (pin "6") (pinfunction "QSTRT_6") (pintype "input"))
      (node (ref "U4") (pin "9") (pinfunction "EP_9") (pintype "power_in"))
    )
    (net (code "14") (name "I2C_PW") (class "Default")
      (node (ref "C1") (pin "1") (pinfunction "1_1") (pintype "passive"))
      (node (ref "C2") (pin "1") (pinfunction "1_1") (pintype "passive"))
      (node (ref "R1_PINH") (pin "2") (pinfunction "2_2") (pintype "passive"))
      (node (ref "R2-PINH") (pin "2") (pinfunction "2_2") (pintype "passive"))
      (node (ref "SENSOR2") (pin "2") (pinfunction "CSB_2") (pintype "input"))
      (node (ref "SENSOR2") (pin "6") (pinfunction "VDDIO_6") (pintype "power_in"))
      (node (ref "SENSOR2") (pin "8") (pinfunction "VDD_8") (pintype "power_in"))
      (node (ref "U2") (pin "17") (pinfunction "IO19_17") (pintype "bidirectional"))
    )
    (net (code "15") (name "INT_RTC") (class "Default")
      (node (ref "R1_PINH1") (pin "1") (pinfunction "1_1") (pintype "passive"))
      (node (ref "TP15") (pin "TP") (pinfunction "TP_TP") (pintype "input"))
      (node (ref "U2") (pin "8") (pinfunction "IO0_8") (pintype "bidirectional"))
      (node (ref "U3") (pin "3") (pinfunction "SQW/~{INT}_3") (pintype "output"))
    )
    (net (code "16") (name "IO{slash}BOOT") (class "Default")
      (node (ref "BOOT_BUTTON") (pin "3") (pinfunction "3_3") (pintype "passive"))
      (node (ref "BOOT_BUTTON") (pin "4") (pinfunction "4_4") (pintype "passive"))
      (node (ref "C6") (pin "1") (pinfunction "1_1") (pintype "passive"))
      (node (ref "R_BOOT") (pin "2") (pinfunction "2_2") (pintype "passive"))
    )
    (net (code "17") (name "IO{slash}CHANGE") (class "Default")
      (node (ref "C10") (pin "1") (pinfunction "1_1") (pintype "passive"))
      (node (ref "CHANGE_BUTTON") (pin "3") (pinfunction "3_3") (pintype "passive"))
      (node (ref "CHANGE_BUTTON") (pin "4") (pinfunction "4_4") (pintype "passive"))
      (node (ref "R_CHANGE") (pin "2") (pinfunction "2_2") (pintype "passive"))
      (node (ref "U2") (pin "23") (pinfunction "IO15_23") (pintype "bidirectional"))
    )
    (net (code "18") (name "MISO") (class "Default")
      (node (ref "D12") (pin "2") (pinfunction "2_2") (pintype "passive"))
      (node (ref "J4") (pin "P7") (pinfunction "DAT0_P7") (pintype "bidirectional"))
      (node (ref "R8") (pin "1") (pinfunction "1_1") (pintype "passive"))
      (node (ref "TP6") (pin "TP") (pinfunction "TP_TP") (pintype "input"))
      (node (ref "U1") (pin "2") (pinfunction "DO(IO1)_2") (pintype "bidirectional"))
      (node (ref "U2") (pin "27") (pinfunction "IO2_27") (pintype "bidirectional"))
    )
    (net (code "19") (name "MOSI") (class "Default")
      (node (ref "D11") (pin "2") (pinfunction "2_2") (pintype "passive"))
      (node (ref "J1") (pin "14") (pinfunction "14_14") (pintype "bidirectional"))
      (node (ref "J4") (pin "P3") (pinfunction "CMD_P3") (pintype "bidirectional"))
      (node (ref "R7") (pin "1") (pinfunction "1_1") (pintype "passive"))
      (node (ref "TP7") (pin "TP") (pinfunction "TP_TP") (pintype "input"))
      (node (ref "U1") (pin "5") (pinfunction "DI(IO0)_5") (pintype "bidirectional"))
      (node (ref "U2") (pin "7") (pinfunction "IO7_7") (pintype "bidirectional"))
    )
    (net (code "20") (name "N$28") (class "Default")
      (node (ref "R1") (pin "2") (pinfunction "2_2") (pintype "passive"))
      (node (ref "U2") (pin "10") (pinfunction "IO8_10") (pintype "bidirectional"))
    )
    (net (code "21") (name "Net-(CHG_LED-PadC)") (class "Default")
      (node (ref "CHG_LED") (pin "C") (pinfunction "C_C") (pintype "passive"))
      (node (ref "R1_BAT") (pin "1") (pinfunction "1_1") (pintype "passive"))
    )
    (net (code "22") (name "Net-(D2-CATHODE)") (class "Default")
      (node (ref "C1_BAT1") (pin "1") (pinfunction "1_1") (pintype "passive"))
      (node (ref "D2") (pin "1") (pinfunction "CATHODE_1") (pintype "bidirectional"))
      (node (ref "IC2") (pin "1") (pinfunction "VIN_1") (pintype "bidirectional"))
      (node (ref "IC2") (pin "3") (pinfunction "CE_3") (pintype "bidirectional"))
      (node (ref "Q3") (pin "2") (pinfunction "S_2") (pintype "bidirectional"))
    )
    (net (code "23") (name "Net-(D3-A)") (class "Default")
      (node (ref "C4") (pin "1") (pinfunction "1_1") (pintype "passive"))
      (node (ref "D3") (pin "2") (pinfunction "A_2") (pintype "bidirectional"))
      (node (ref "D4") (pin "1") (pinfunction "K_1") (pintype "bidirectional"))
    )
    (net (code "24") (name "Net-(D7-CATHODE)") (class "Default")
      (node (ref "D7") (pin "1") (pinfunction "CATHODE_1") (pintype "bidirectional"))
      (node (ref "R_CAPACITOR") (pin "2") (pinfunction "2_2") (pintype "passive"))
    )
    (net (code "25") (name "Net-(EPD_C1-Pad1)") (class "Default")
      (node (ref "EPD_C1") (pin "1") (pinfunction "1_1") (pintype "passive"))
      (node (ref "J1") (pin "4") (pinfunction "4_4") (pintype "bidirectional"))
    )
    (net (code "26") (name "Net-(EPD_C2-Pad1)") (class "Default")
      (node (ref "EPD_C2") (pin "1") (pinfunction "1_1") (pintype "passive"))
      (node (ref "J1") (pin "5") (pinfunction "5_5") (pintype "bidirectional"))
    )
    (net (code "27") (name "Net-(EPD_C6-Pad1)") (class "Default")
      (node (ref "EPD_C6") (pin "1") (pinfunction "1_1") (pintype "passive"))
      (node (ref "J1") (pin "18") (pinfunction "18_18") (pintype "bidirectional"))
    )
    (net (code "28") (name "Net-(EPD_C7-Pad1)") (class "Default")
      (node (ref "EPD_C7") (pin "1") (pinfunction "1_1") (pintype "passive"))
      (node (ref "J1") (pin "19") (pinfunction "19_19") (pintype "bidirectional"))
    )
    (net (code "29") (name "Net-(EPD_C8-Pad1)") (class "Default")
      (node (ref "EPD_C8") (pin "1") (pinfunction "1_1") (pintype "passive"))
      (node (ref "J1") (pin "20") (pinfunction "20_20") (pintype "bidirectional"))
    )
    (net (code "30") (name "Net-(EPD_C10-Pad1)") (class "Default")
      (node (ref "EPD_C10") (pin "1") (pinfunction "1_1") (pintype "passive"))
      (node (ref "J1") (pin "22") (pinfunction "22_22") (pintype "bidirectional"))
    )
    (net (code "31") (name "Net-(EPD_C12-Pad1)") (class "Default")
      (node (ref "EPD_C12") (pin "1") (pinfunction "1_1") (pintype "passive"))
      (node (ref "J1") (pin "24") (pinfunction "24_24") (pintype "bidirectional"))
    )
    (net (code "32") (name "Net-(IC1-CT)") (class "Default")
      (node (ref "C_DELAY") (pin "1") (pinfunction "1_1") (pintype "passive"))
      (node (ref "IC1") (pin "5") (pinfunction "CT_5") (pintype "bidirectional"))
    )
    (net (code "33") (name "Net-(J2-PadA5)") (class "Default")
      (node (ref "J2") (pin "A5") (pinfunction "A5_A5") (pintype "bidirectional"))
      (node (ref "R2-USB1") (pin "2") (pinfunction "2_2") (pintype "passive"))
    )
    (net (code "34") (name "Net-(J2-PadB5)") (class "Default")
      (node (ref "J2") (pin "B5") (pinfunction "B5_B5") (pintype "bidirectional"))
      (node (ref "R2-USB") (pin "1") (pinfunction "1_1") (pintype "passive"))
    )
    (net (code "35") (name "Net-(MCP73831-PROG)") (class "Default")
      (node (ref "MCP73831") (pin "5") (pinfunction "PROG_5") (pintype "input"))
      (node (ref "R2_BAT") (pin "2") (pinfunction "2_2") (pintype "passive"))
    )
    (net (code "36") (name "Net-(MCP73831-STAT)") (class "Default")
      (node (ref "MCP73831") (pin "1") (pinfunction "STAT_1") (pintype "output"))
      (node (ref "R1_BAT") (pin "2") (pinfunction "2_2") (pintype "passive"))
    )
    (net (code "37") (name "PREVGH") (class "Default")
      (node (ref "D5") (pin "1") (pinfunction "K_1") (pintype "bidirectional"))
      (node (ref "EPD_C9") (pin "1") (pinfunction "1_1") (pintype "passive"))
      (node (ref "J1") (pin "21") (pinfunction "21_21") (pintype "bidirectional"))
    )
    (net (code "38") (name "PREVGL") (class "Default")
      (node (ref "D4") (pin "2") (pinfunction "A_2") (pintype "bidirectional"))
      (node (ref "EPD_C11") (pin "1") (pinfunction "1_1") (pintype "passive"))
      (node (ref "J1") (pin "23") (pinfunction "23_23") (pintype "bidirectional"))
    )
    (net (code "39") (name "RESE") (class "Default")
      (node (ref "J1") (pin "3") (pinfunction "3_3") (pintype "bidirectional"))
      (node (ref "Q1") (pin "2") (pinfunction "S_2") (pintype "bidirectional"))
      (node (ref "R3") (pin "1") (pinfunction "1_1") (pintype "passive"))
    )
    (net (code "40") (name "RESE'") (class "Default")
      (node (ref "R2") (pin "2") (pinfunction "2_2") (pintype "passive"))
      (node (ref "R3") (pin "2") (pinfunction "2_2") (pintype "passive"))
      (node (ref "SJ1") (pin "2") (pinfunction "2_2") (pintype "passive"))
    )
    (net (code "41") (name "RESET") (class "Default")
      (node (ref "C5") (pin "1") (pinfunction "1_1") (pintype "passive"))
      (node (ref "IC1") (pin "1") (pinfunction "VOUT_1") (pintype "bidirectional"))
      (node (ref "RESET_BUTTON") (pin "3") (pinfunction "3_3") (pintype "passive"))
      (node (ref "RESET_BUTTON") (pin "4") (pinfunction "4_4") (pintype "passive"))
      (node (ref "R_RESET") (pin "2") (pinfunction "2_2") (pintype "passive"))
      (node (ref "U2") (pin "3") (pinfunction "EN_3") (pintype "input"))
    )
    (net (code "42") (name "RTC_RST") (class "Default")
      (node (ref "U2") (pin "16") (pinfunction "IO18_16") (pintype "bidirectional"))
      (node (ref "U3") (pin "4") (pinfunction "~{RST}_4") (pintype "input"))
    )
    (net (code "43") (name "RX") (class "Default")
      (node (ref "TP2") (pin "TP") (pinfunction "TP_TP") (pintype "input"))
      (node (ref "U2") (pin "24") (pinfunction "RXD0/GPIO17_24") (pintype "bidirectional"))
    )
    (net (code "44") (name "SCK") (class "Default")
      (node (ref "D10") (pin "2") (pinfunction "2_2") (pintype "passive"))
      (node (ref "J1") (pin "13") (pinfunction "13_13") (pintype "bidirectional"))
      (node (ref "J4") (pin "P5") (pinfunction "CLK_P5") (pintype "bidirectional"))
      (node (ref "R6") (pin "1") (pinfunction "1_1") (pintype "passive"))
      (node (ref "TP8") (pin "TP") (pinfunction "TP_TP") (pintype "input"))
      (node (ref "U1") (pin "6") (pinfunction "CLK_6") (pintype "input"))
      (node (ref "U2") (pin "6") (pinfunction "IO6_6") (pintype "bidirectional"))
    )
    (net (code "45") (name "SCL") (class "Default")
      (node (ref "J3") (pin "4") (pinfunction "4_4") (pintype "passive"))
      (node (ref "R2-PINH") (pin "1") (pinfunction "1_1") (pintype "passive"))
      (node (ref "SENSOR2") (pin "4") (pinfunction "SCK_4") (pintype "input"))
      (node (ref "U2") (pin "20") (pinfunction "IO22_20") (pintype "bidirectional"))
      (node (ref "U3") (pin "16") (pinfunction "SCL_16") (pintype "input"))
      (node (ref "U4") (pin "7") (pinfunction "SCL_7") (pintype "input"))
    )
    (net (code "46") (name "SDA") (class "Default")
      (node (ref "J3") (pin "3") (pinfunction "3_3") (pintype "passive"))
      (node (ref "R1_PINH") (pin "1") (pinfunction "1_1") (pintype "passive"))
      (node (ref "SENSOR2") (pin "3") (pinfunction "SDI_3") (pintype "bidirectional"))
      (node (ref "U2") (pin "19") (pinfunction "IO21_19") (pintype "bidirectional"))
      (node (ref "U3") (pin "15") (pinfunction "SDA_15") (pintype "bidirectional"))
      (node (ref "U4") (pin "8") (pinfunction "SDA_8") (pintype "bidirectional"))
    )
    (net (code "47") (name "SRC") (class "Default")
      (node (ref "C4") (pin "2") (pinfunction "2_2") (pintype "passive"))
      (node (ref "D5") (pin "2") (pinfunction "A_2") (pintype "bidirectional"))
      (node (ref "L1") (pin "1") (pinfunction "1_1") (pintype "passive"))
      (node (ref "Q1") (pin "3") (pinfunction "D_3") (pintype "bidirectional"))
    )
    (net (code "48") (name "SS_SD") (class "Default")
      (node (ref "D8") (pin "2") (pinfunction "2_2") (pintype "passive"))
      (node (ref "J4") (pin "P2") (pinfunction "CD/DAT3_P2") (pintype "bidirectional"))
      (node (ref "R10") (pin "1") (pinfunction "1_1") (pintype "passive"))
      (node (ref "U2") (pin "4") (pinfunction "IO4_4") (pintype "bidirectional"))
    )
    (net (code "49") (name "TX") (class "Default")
      (node (ref "TP1") (pin "TP") (pinfunction "TP_TP") (pintype "input"))
      (node (ref "U2") (pin "25") (pinfunction "TXD0/GPIO16_25") (pintype "bidirectional"))
    )
    (net (code "50") (name "USB_D+") (class "Default")
      (node (ref "D1") (pin "1") (pinfunction "I/O1_1_1") (pintype "bidirectional"))
      (node (ref "U2") (pin "14") (pinfunction "IO13_14") (pintype "bidirectional"))
    )
    (net (code "51") (name "USB_D-") (class "Default")
      (node (ref "D1") (pin "3") (pinfunction "I/O2_1_3") (pintype "bidirectional"))
      (node (ref "U2") (pin "13") (pinfunction "IO12_13") (pintype "bidirectional"))
    )
    (net (code "52") (name "VBAT") (class "Default")
      (node (ref "C2_BAT") (pin "1") (pinfunction "1_1") (pintype "passive"))
      (node (ref "MCP73831") (pin "3") (pinfunction "VBAT_3") (pintype "power_in"))
      (node (ref "Q3") (pin "3") (pinfunction "D_3") (pintype "bidirectional"))
      (node (ref "TP3") (pin "TP") (pinfunction "TP_TP") (pintype "input"))
      (node (ref "U4") (pin "2") (pinfunction "CELL_2") (pintype "power_in"))
      (node (ref "U4") (pin "3") (pinfunction "VDD_3") (pintype "power_in"))
    )
    (net (code "53") (name "VBUS") (class "Default")
      (node (ref "C1_BAT") (pin "1") (pinfunction "1_1") (pintype "passive"))
      (node (ref "C4_USB") (pin "1") (pinfunction "1_1") (pintype "passive"))
      (node (ref "C5_USB") (pin "1") (pinfunction "1_1") (pintype "passive"))
      (node (ref "CHG_LED") (pin "A") (pinfunction "A_A") (pintype "passive"))
      (node (ref "D1") (pin "5") (pinfunction "VBUS_5") (pintype "bidirectional"))
      (node (ref "D2") (pin "2") (pinfunction "ANODE_2") (pintype "bidirectional"))
      (node (ref "MCP73831") (pin "4") (pinfunction "VIN_4") (pintype "power_in"))
      (node (ref "PFMF.050.1") (pin "2") (pinfunction "2_2") (pintype "passive"))
      (node (ref "Q3") (pin "1") (pinfunction "G_1") (pintype "bidirectional"))
      (node (ref "R1_PWRUSB") (pin "2") (pinfunction "2_2") (pintype "passive"))
      (node (ref "TP14") (pin "TP") (pinfunction "TP_TP") (pintype "input"))
    )
    (net (code "54") (name "VRTC") (class "Default")
      (node (ref "C10_SUPERCAP") (pin "1") (pinfunction "1_1") (pintype "passive"))
      (node (ref "C8") (pin "1") (pinfunction "1_1") (pintype "passive"))
      (node (ref "R_CAPACITOR") (pin "1") (pinfunction "1_1") (pintype "passive"))
      (node (ref "U3") (pin "14") (pinfunction "VBAT_14") (pintype "power_in"))
    )
    (net (code "55") (name "VUSB") (class "Default")
      (node (ref "J2") (pin "A4") (pinfunction "A4_A4") (pintype "bidirectional"))
      (node (ref "J2") (pin "A9") (pinfunction "A9_A9") (pintype "bidirectional"))
      (node (ref "J2") (pin "B4") (pinfunction "B4_B4") (pintype "bidirectional"))
      (node (ref "J2") (pin "B9") (pinfunction "B9_B9") (pintype "bidirectional"))
      (node (ref "PFMF.050.1") (pin "1") (pinfunction "1_1") (pintype "passive"))
    )
    (net (code "56") (name "unconnected-(IC1-NC-Pad4)") (class "Default")
      (node (ref "IC1") (pin "4") (pinfunction "NC_4") (pintype "no_connect"))
    )
    (net (code "57") (name "unconnected-(IC2-NC-Pad4)") (class "Default")
      (node (ref "IC2") (pin "4") (pinfunction "NC_4") (pintype "no_connect"))
    )
    (net (code "58") (name "unconnected-(J1-Pad1)") (class "Default")
      (node (ref "J1") (pin "1") (pinfunction "1_1") (pintype "bidirectional"))
    )
    (net (code "59") (name "unconnected-(J1-Pad6)") (class "Default")
      (node (ref "J1") (pin "6") (pinfunction "6_6") (pintype "bidirectional"))
    )
    (net (code "60") (name "unconnected-(J1-Pad7)") (class "Default")
      (node (ref "J1") (pin "7") (pinfunction "7_7") (pintype "bidirectional"))
    )
    (net (code "61") (name "unconnected-(J2-PadA8)") (class "Default")
      (node (ref "J2") (pin "A8") (pinfunction "A8_A8") (pintype "bidirectional"))
    )
    (net (code "62") (name "unconnected-(J2-PadB8)") (class "Default")
      (node (ref "J2") (pin "B8") (pinfunction "B8_B8") (pintype "bidirectional"))
    )
    (net (code "63") (name "unconnected-(J4-DAT1-PadP8)") (class "Default")
      (node (ref "J4") (pin "P8") (pinfunction "DAT1_P8") (pintype "bidirectional"))
    )
    (net (code "64") (name "unconnected-(J4-DAT2-PadP1)") (class "Default")
      (node (ref "J4") (pin "P1") (pinfunction "DAT2_P1") (pintype "bidirectional"))
    )
    (net (code "65") (name "unconnected-(J4-DETECTION_1-PadS1)") (class "Default")
      (node (ref "J4") (pin "S1") (pinfunction "DETECTION_1_S1") (pintype "bidirectional"))
    )
    (net (code "66") (name "unconnected-(J4-DETECTION_2-PadS2)") (class "Default")
      (node (ref "J4") (pin "S2") (pinfunction "DETECTION_2_S2") (pintype "bidirectional"))
    )
    (net (code "67") (name "unconnected-(U2-NC-Pad22)") (class "Default")
      (node (ref "U2") (pin "22") (pinfunction "NC_22") (pintype "no_connect"))
    )
    (net (code "68") (name "unconnected-(U4-~{ALERT}-Pad5)") (class "Default")
      (node (ref "U4") (pin "5") (pinfunction "~{ALERT}_5") (pintype "output"))
    )
  )
)
